# 04_Sensors.net
KiCad netlist of a schematic drawn in Altium Designer
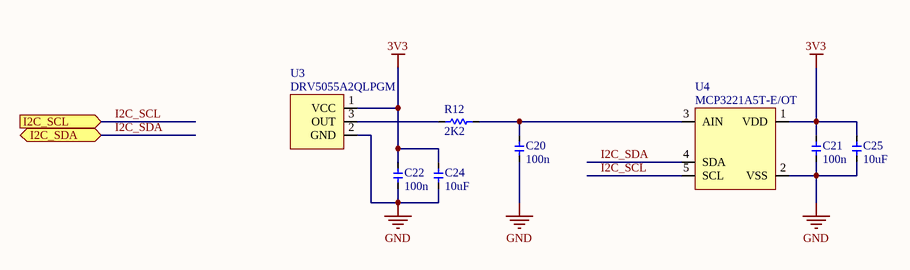
[diagram p0: 04_Sensors.SchDoc]

(export (version "E")
  (design (tool "Eeschema 10.0.6"))
  (components
    (comp (ref "C20")
      (value "100n")
      (footprint "Footprint_Misc:0603 - CAP")
      (description "Capacitor")
      (fields
        (field (name "MANUFACTURER") "Samsung Electro-Mechanics")
        (field (name "MANUFACTURER PART NUMBER") "CL10B104KB8NNNC")
      )
      (libsource (lib "Schematic_Misc") (part "Cap"))
    )
    (comp (ref "C21")
      (value "100n")
      (footprint "Footprint_Misc:0603 - CAP")
      (description "Capacitor")
      (fields
        (field (name "MANUFACTURER") "Samsung Electro-Mechanics")
        (field (name "MANUFACTURER PART NUMBER") "CL10B104KB8NNNC")
      )
      (libsource (lib "Schematic_Misc") (part "Cap"))
    )
    (comp (ref "C22")
      (value "100n")
      (footprint "Footprint_Misc:0603 - CAP")
      (description "Capacitor")
      (fields
        (field (name "MANUFACTURER") "Samsung Electro-Mechanics")
        (field (name "MANUFACTURER PART NUMBER") "CL10B104KB8NNNC")
      )
      (libsource (lib "Schematic_Misc") (part "Cap"))
    )
    (comp (ref "C24")
      (value "10uF")
      (footprint "Footprint_Misc:0603 - CAP")
      (description "Capacitor")
      (fields
        (field (name "MANUFACTURER") "Samsung Electro-Mechanics")
        (field (name "MANUFACTURER PART NUMBER") "CL21A106KAYNNNE")
      )
      (libsource (lib "Schematic_Misc") (part "Cap"))
    )
    (comp (ref "C25")
      (value "10uF")
      (footprint "Footprint_Misc:0603 - CAP")
      (description "Capacitor")
      (fields
        (field (name "MANUFACTURER") "Samsung Electro-Mechanics")
        (field (name "MANUFACTURER PART NUMBER") "CL21A106KAYNNNE")
      )
      (libsource (lib "Schematic_Misc") (part "Cap"))
    )
    (comp (ref "R12")
      (value "2K2")
      (footprint "Footprint_Misc:0603")
      (description "Resistor")
      (fields (field (name "DISTRIBUTOR PART NUMBER") "C125931") (field (name "MANUFACTURER") "YAGEO"))
      (libsource (lib "Schematic_Misc") (part "Res"))
    )
    (comp (ref "U3")
      (value "DRV5055A2QLPGM")
      (footprint "Footprint_Misc:SS490A")
      (description "Hall Effect Sensor Single Axis Radial Lead")
      (fields
        (field (name "MANUFACTURER") "Texas Instruments")
        (field (name "MANUFACTURER PART NUMBER") "DRV5055A3QLPGM")
      )
      (libsource (lib "Schematic_Misc") (part "DRV5055A2QLPGM"))
    )
    (comp (ref "U4")
      (value "MCP3221A5T-E/OT")
      (footprint "Footprint_Misc:SOT95P270X145-5N")
      (description "10 Bit Analog to Digital Converter 1 Input 1 SAR SOT-23-5")
      (fields
        (field (name "MANUFACTURER") "Microchip Technology")
        (field (name "DISTRIBUTOR PART NUMBER") "C625475")
      )
      (libsource (lib "Schematic_Misc") (part "MCP3021A5T-E/OT"))
    )
  )
  (nets
    (net (code "1") (name "/I2C_SCL") (class "Default")
      (node (ref "U4") (pin "5") (pinfunction "SCL_5") (pintype "passive"))
    )
    (net (code "2") (name "/I2C_SDA") (class "Default")
      (node (ref "U4") (pin "4") (pinfunction "SDA_4") (pintype "passive"))
    )
    (net (code "3") (name "3V3") (class "Default")
      (node (ref "C21") (pin "2") (pinfunction "2_2") (pintype "passive"))
      (node (ref "C22") (pin "2") (pinfunction "2_2") (pintype "passive"))
      (node (ref "C24") (pin "2") (pinfunction "2_2") (pintype "passive"))
      (node (ref "C25") (pin "2") (pinfunction "2_2") (pintype "passive"))
      (node (ref "U3") (pin "1") (pinfunction "VCC_1") (pintype "passive"))
      (node (ref "U4") (pin "1") (pinfunction "VDD_1") (pintype "passive"))
    )
    (net (code "4") (name "GND") (class "Default")
      (node (ref "C20") (pin "1") (pinfunction "1_1") (pintype "passive"))
      (node (ref "C21") (pin "1") (pinfunction "1_1") (pintype "passive"))
      (node (ref "C22") (pin "1") (pinfunction "1_1") (pintype "passive"))
      (node (ref "C24") (pin "1") (pinfunction "1_1") (pintype "passive"))
      (node (ref "C25") (pin "1") (pinfunction "1_1") (pintype "passive"))
      (node (ref "U3") (pin "2") (pinfunction "GND_2") (pintype "passive"))
      (node (ref "U4") (pin "2") (pinfunction "VSS_2") (pintype "passive"))
    )
    (net (code "5") (name "Net-(U3-OUT)") (class "Default")
      (node (ref "R12") (pin "1") (pinfunction "1_1") (pintype "passive"))
      (node (ref "U3") (pin "3") (pinfunction "OUT_3") (pintype "passive"))
    )
    (net (code "6") (name "Net-(U4-AIN)") (class "Default")
      (node (ref "C20") (pin "2") (pinfunction "2_2") (pintype "passive"))
      (node (ref "R12") (pin "2") (pinfunction "2_2") (pintype "passive"))
      (node (ref "U4") (pin "3") (pinfunction "AIN_3") (pintype "passive"))
    )
  )
)
